# ME433.net
KiCad netlist of a schematic drawn in EAGLE
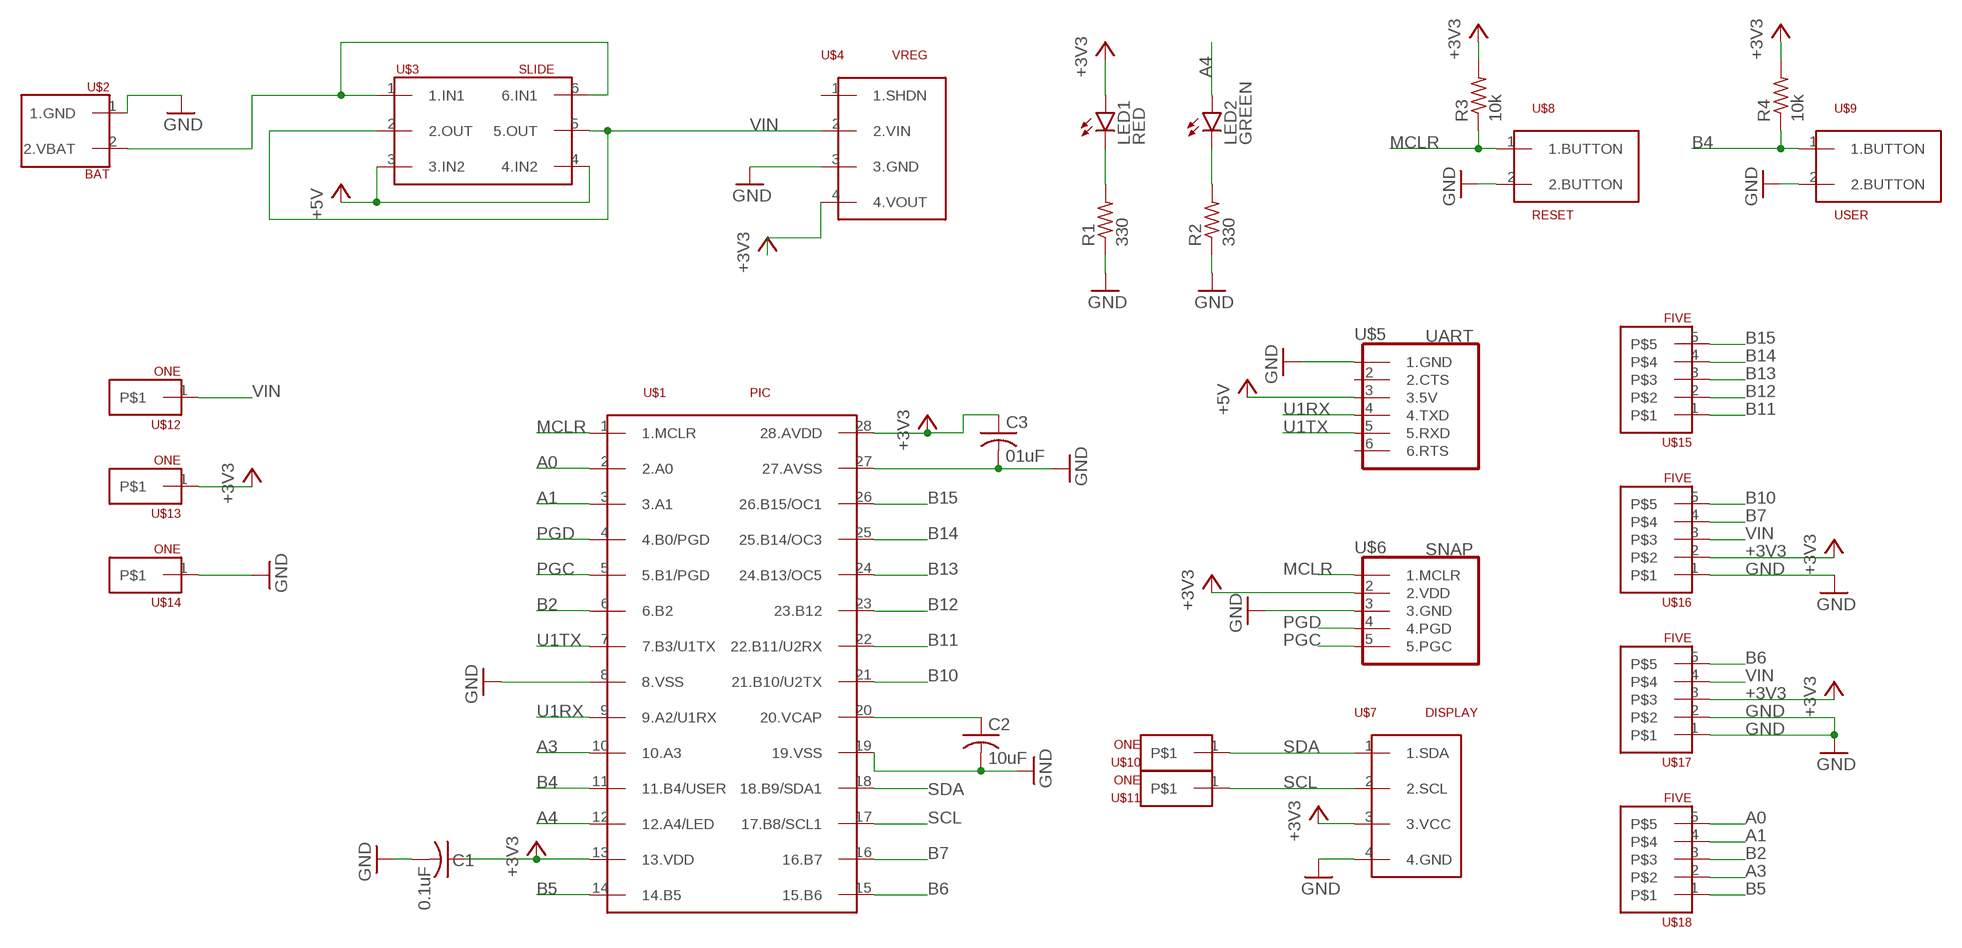
[diagram p0: schematic, sheet 1]

(export (version "E")
  (design (tool "Eeschema 10.0.6"))
  (components
    (comp (ref "C1")
      (value "0.1uF")
      (footprint "eagle-import:C025-024X044")
      (libsource (lib "eagle-import") (part "C-US025-024X044"))
    )
    (comp (ref "C2")
      (value "10uF")
      (footprint "eagle-import:C025-024X044")
      (libsource (lib "eagle-import") (part "C-US025-024X044"))
    )
    (comp (ref "C3")
      (value "01uF")
      (footprint "eagle-import:C025-024X044")
      (libsource (lib "eagle-import") (part "C-US025-024X044"))
    )
    (comp (ref "LED1")
      (value "RED")
      (footprint "eagle-import:LED3MM")
      (libsource (lib "eagle-import") (part "LED3MM"))
    )
    (comp (ref "LED2")
      (value "GREEN")
      (footprint "eagle-import:LED3MM")
      (libsource (lib "eagle-import") (part "LED3MM"))
    )
    (comp (ref "R1")
      (value "330")
      (footprint "eagle-import:0207_7")
      (libsource (lib "eagle-import") (part "R-US_0207/7"))
    )
    (comp (ref "R2")
      (value "330")
      (footprint "eagle-import:0207_7")
      (libsource (lib "eagle-import") (part "R-US_0207/7"))
    )
    (comp (ref "R3")
      (value "10k")
      (footprint "eagle-import:0207_7")
      (libsource (lib "eagle-import") (part "R-US_0207/7"))
    )
    (comp (ref "R4")
      (value "10k")
      (footprint "eagle-import:0207_7")
      (libsource (lib "eagle-import") (part "R-US_0207/7"))
    )
    (comp (ref "U$1")
      (value "PIC")
      (footprint "eagle-import:DIL28-3")
      (libsource (lib "eagle-import") (part "PIC"))
    )
    (comp (ref "U$2")
      (value "BAT")
      (footprint "eagle-import:BAT")
      (libsource (lib "eagle-import") (part "BAT"))
    )
    (comp (ref "U$3")
      (value "SLIDE")
      (footprint "eagle-import:SLIDE")
      (libsource (lib "eagle-import") (part "SLIDE"))
    )
    (comp (ref "U$4")
      (value "VREG")
      (footprint "eagle-import:VREG")
      (libsource (lib "eagle-import") (part "VREG"))
    )
    (comp (ref "U$5")
      (value "UART")
      (footprint "eagle-import:UART")
      (libsource (lib "eagle-import") (part "UART"))
    )
    (comp (ref "U$6")
      (value "SNAP")
      (footprint "eagle-import:SNAP")
      (libsource (lib "eagle-import") (part "SNAP"))
    )
    (comp (ref "U$7")
      (value "DISPLAY")
      (footprint "eagle-import:DISPLAY")
      (libsource (lib "eagle-import") (part "DISPLAY"))
    )
    (comp (ref "U$8")
      (value "RESET")
      (footprint "eagle-import:BUTTON")
      (libsource (lib "eagle-import") (part "BUTTON"))
    )
    (comp (ref "U$9")
      (value "USER")
      (footprint "eagle-import:BUTTON")
      (libsource (lib "eagle-import") (part "BUTTON"))
    )
    (comp (ref "U$10")
      (value "ONE")
      (footprint "eagle-import:ONE")
      (libsource (lib "eagle-import") (part "ONE"))
    )
    (comp (ref "U$11")
      (value "ONE")
      (footprint "eagle-import:ONE")
      (libsource (lib "eagle-import") (part "ONE"))
    )
    (comp (ref "U$12")
      (value "ONE")
      (footprint "eagle-import:ONE")
      (libsource (lib "eagle-import") (part "ONE"))
    )
    (comp (ref "U$13")
      (value "ONE")
      (footprint "eagle-import:ONE")
      (libsource (lib "eagle-import") (part "ONE"))
    )
    (comp (ref "U$14")
      (value "ONE")
      (footprint "eagle-import:ONE")
      (libsource (lib "eagle-import") (part "ONE"))
    )
    (comp (ref "U$15")
      (value "FIVE")
      (footprint "eagle-import:FIVE")
      (libsource (lib "eagle-import") (part "FIVE"))
    )
    (comp (ref "U$16")
      (value "FIVE")
      (footprint "eagle-import:FIVE")
      (libsource (lib "eagle-import") (part "FIVE"))
    )
    (comp (ref "U$17")
      (value "FIVE")
      (footprint "eagle-import:FIVE")
      (libsource (lib "eagle-import") (part "FIVE"))
    )
    (comp (ref "U$18")
      (value "FIVE")
      (footprint "eagle-import:FIVE")
      (libsource (lib "eagle-import") (part "FIVE"))
    )
  )
  (nets
    (net (code "1") (name "+3V3") (class "Default")
      (node (ref "C1") (pin "1") (pinfunction "1_1") (pintype "passive"))
      (node (ref "C3") (pin "1") (pinfunction "1_1") (pintype "passive"))
      (node (ref "LED1") (pin "A") (pinfunction "A_A") (pintype "passive"))
      (node (ref "R3") (pin "2") (pinfunction "2_2") (pintype "passive"))
      (node (ref "R4") (pin "2") (pinfunction "2_2") (pintype "passive"))
      (node (ref "U$1") (pin "13") (pinfunction "13.VDD_13") (pintype "bidirectional"))
      (node (ref "U$1") (pin "28") (pinfunction "28.AVDD_28") (pintype "bidirectional"))
      (node (ref "U$13") (pin "1") (pinfunction "P$1_1") (pintype "bidirectional"))
      (node (ref "U$16") (pin "2") (pinfunction "P$2_2") (pintype "bidirectional"))
      (node (ref "U$17") (pin "3") (pinfunction "P$3_3") (pintype "bidirectional"))
      (node (ref "U$4") (pin "4") (pinfunction "4.VOUT_4") (pintype "bidirectional"))
      (node (ref "U$6") (pin "2") (pinfunction "2.VDD_2") (pintype "bidirectional"))
      (node (ref "U$7") (pin "3") (pinfunction "3.VCC_3") (pintype "bidirectional"))
    )
    (net (code "2") (name "+5V") (class "Default")
      (node (ref "U$3") (pin "3") (pinfunction "3.IN2_3") (pintype "bidirectional"))
      (node (ref "U$3") (pin "4") (pinfunction "4.IN2_4") (pintype "bidirectional"))
      (node (ref "U$5") (pin "3") (pinfunction "3.5V_3") (pintype "bidirectional"))
    )
    (net (code "3") (name "/A0") (class "Default")
      (node (ref "U$1") (pin "2") (pinfunction "2.A0_2") (pintype "bidirectional"))
      (node (ref "U$18") (pin "5") (pinfunction "P$5_5") (pintype "bidirectional"))
    )
    (net (code "4") (name "/A1") (class "Default")
      (node (ref "U$1") (pin "3") (pinfunction "3.A1_3") (pintype "bidirectional"))
      (node (ref "U$18") (pin "4") (pinfunction "P$4_4") (pintype "bidirectional"))
    )
    (net (code "5") (name "/A3") (class "Default")
      (node (ref "U$1") (pin "10") (pinfunction "10.A3_10") (pintype "bidirectional"))
      (node (ref "U$18") (pin "2") (pinfunction "P$2_2") (pintype "bidirectional"))
    )
    (net (code "6") (name "/A4") (class "Default")
      (node (ref "LED2") (pin "A") (pinfunction "A_A") (pintype "passive"))
      (node (ref "U$1") (pin "12") (pinfunction "12.A4/LED_12") (pintype "bidirectional"))
    )
    (net (code "7") (name "/B2") (class "Default")
      (node (ref "U$1") (pin "6") (pinfunction "6.B2_6") (pintype "bidirectional"))
      (node (ref "U$18") (pin "3") (pinfunction "P$3_3") (pintype "bidirectional"))
    )
    (net (code "8") (name "/B4") (class "Default")
      (node (ref "R4") (pin "1") (pinfunction "1_1") (pintype "passive"))
      (node (ref "U$1") (pin "11") (pinfunction "11.B4/USER_11") (pintype "bidirectional"))
      (node (ref "U$9") (pin "1") (pinfunction "1.BUTTON_1") (pintype "bidirectional"))
    )
    (net (code "9") (name "/B5") (class "Default")
      (node (ref "U$1") (pin "14") (pinfunction "14.B5_14") (pintype "bidirectional"))
      (node (ref "U$18") (pin "1") (pinfunction "P$1_1") (pintype "bidirectional"))
    )
    (net (code "10") (name "/B6") (class "Default")
      (node (ref "U$1") (pin "15") (pinfunction "15.B6_15") (pintype "bidirectional"))
      (node (ref "U$17") (pin "5") (pinfunction "P$5_5") (pintype "bidirectional"))
    )
    (net (code "11") (name "/B7") (class "Default")
      (node (ref "U$1") (pin "16") (pinfunction "16.B7_16") (pintype "bidirectional"))
      (node (ref "U$16") (pin "4") (pinfunction "P$4_4") (pintype "bidirectional"))
    )
    (net (code "12") (name "/B10") (class "Default")
      (node (ref "U$1") (pin "21") (pinfunction "21.B10/U2TX_21") (pintype "bidirectional"))
      (node (ref "U$16") (pin "5") (pinfunction "P$5_5") (pintype "bidirectional"))
    )
    (net (code "13") (name "/B11") (class "Default")
      (node (ref "U$1") (pin "22") (pinfunction "22.B11/U2RX_22") (pintype "bidirectional"))
      (node (ref "U$15") (pin "1") (pinfunction "P$1_1") (pintype "bidirectional"))
    )
    (net (code "14") (name "/B12") (class "Default")
      (node (ref "U$1") (pin "23") (pinfunction "23.B12_23") (pintype "bidirectional"))
      (node (ref "U$15") (pin "2") (pinfunction "P$2_2") (pintype "bidirectional"))
    )
    (net (code "15") (name "/B13") (class "Default")
      (node (ref "U$1") (pin "24") (pinfunction "24.B13/OC5_24") (pintype "bidirectional"))
      (node (ref "U$15") (pin "3") (pinfunction "P$3_3") (pintype "bidirectional"))
    )
    (net (code "16") (name "/B14") (class "Default")
      (node (ref "U$1") (pin "25") (pinfunction "25.B14/OC3_25") (pintype "bidirectional"))
      (node (ref "U$15") (pin "4") (pinfunction "P$4_4") (pintype "bidirectional"))
    )
    (net (code "17") (name "/B15") (class "Default")
      (node (ref "U$1") (pin "26") (pinfunction "26.B15/OC1_26") (pintype "bidirectional"))
      (node (ref "U$15") (pin "5") (pinfunction "P$5_5") (pintype "bidirectional"))
    )
    (net (code "18") (name "/MCLR") (class "Default")
      (node (ref "R3") (pin "1") (pinfunction "1_1") (pintype "passive"))
      (node (ref "U$1") (pin "1") (pinfunction "1.MCLR_1") (pintype "bidirectional"))
      (node (ref "U$6") (pin "1") (pinfunction "1.MCLR_1") (pintype "bidirectional"))
      (node (ref "U$8") (pin "1") (pinfunction "1.BUTTON_1") (pintype "bidirectional"))
    )
    (net (code "19") (name "/PGC") (class "Default")
      (node (ref "U$1") (pin "5") (pinfunction "5.B1/PGD_5") (pintype "bidirectional"))
      (node (ref "U$6") (pin "5") (pinfunction "5.PGC_5") (pintype "bidirectional"))
    )
    (net (code "20") (name "/PGD") (class "Default")
      (node (ref "U$1") (pin "4") (pinfunction "4.B0/PGD_4") (pintype "bidirectional"))
      (node (ref "U$6") (pin "4") (pinfunction "4.PGD_4") (pintype "bidirectional"))
    )
    (net (code "21") (name "/SCL") (class "Default")
      (node (ref "U$1") (pin "17") (pinfunction "17.B8/SCL1_17") (pintype "bidirectional"))
      (node (ref "U$11") (pin "1") (pinfunction "P$1_1") (pintype "bidirectional"))
      (node (ref "U$7") (pin "2") (pinfunction "2.SCL_2") (pintype "bidirectional"))
    )
    (net (code "22") (name "/SDA") (class "Default")
      (node (ref "U$1") (pin "18") (pinfunction "18.B9/SDA1_18") (pintype "bidirectional"))
      (node (ref "U$10") (pin "1") (pinfunction "P$1_1") (pintype "bidirectional"))
      (node (ref "U$7") (pin "1") (pinfunction "1.SDA_1") (pintype "bidirectional"))
    )
    (net (code "23") (name "/U1RX") (class "Default")
      (node (ref "U$1") (pin "9") (pinfunction "9.A2/U1RX_9") (pintype "bidirectional"))
      (node (ref "U$5") (pin "4") (pinfunction "4.TXD_4") (pintype "bidirectional"))
    )
    (net (code "24") (name "/U1TX") (class "Default")
      (node (ref "U$1") (pin "7") (pinfunction "7.B3/U1TX_7") (pintype "bidirectional"))
      (node (ref "U$5") (pin "5") (pinfunction "5.RXD_5") (pintype "bidirectional"))
    )
    (net (code "25") (name "/VIN") (class "Default")
      (node (ref "U$12") (pin "1") (pinfunction "P$1_1") (pintype "bidirectional"))
      (node (ref "U$16") (pin "3") (pinfunction "P$3_3") (pintype "bidirectional"))
      (node (ref "U$17") (pin "4") (pinfunction "P$4_4") (pintype "bidirectional"))
      (node (ref "U$3") (pin "2") (pinfunction "2.OUT_2") (pintype "bidirectional"))
      (node (ref "U$3") (pin "5") (pinfunction "5.OUT_5") (pintype "bidirectional"))
      (node (ref "U$4") (pin "2") (pinfunction "2.VIN_2") (pintype "bidirectional"))
    )
    (net (code "26") (name "GND") (class "Default")
      (node (ref "C1") (pin "2") (pinfunction "2_2") (pintype "passive"))
      (node (ref "C2") (pin "2") (pinfunction "2_2") (pintype "passive"))
      (node (ref "C3") (pin "2") (pinfunction "2_2") (pintype "passive"))
      (node (ref "R1") (pin "1") (pinfunction "1_1") (pintype "passive"))
      (node (ref "R2") (pin "1") (pinfunction "1_1") (pintype "passive"))
      (node (ref "U$1") (pin "19") (pinfunction "19.VSS_19") (pintype "bidirectional"))
      (node (ref "U$1") (pin "27") (pinfunction "27.AVSS_27") (pintype "bidirectional"))
      (node (ref "U$1") (pin "8") (pinfunction "8.VSS_8") (pintype "bidirectional"))
      (node (ref "U$14") (pin "1") (pinfunction "P$1_1") (pintype "bidirectional"))
      (node (ref "U$16") (pin "1") (pinfunction "P$1_1") (pintype "bidirectional"))
      (node (ref "U$17") (pin "1") (pinfunction "P$1_1") (pintype "bidirectional"))
      (node (ref "U$17") (pin "2") (pinfunction "P$2_2") (pintype "bidirectional"))
      (node (ref "U$2") (pin "1") (pinfunction "1.GND_1") (pintype "bidirectional"))
      (node (ref "U$4") (pin "3") (pinfunction "3.GND_3") (pintype "bidirectional"))
      (node (ref "U$5") (pin "1") (pinfunction "1.GND_1") (pintype "bidirectional"))
      (node (ref "U$6") (pin "3") (pinfunction "3.GND_3") (pintype "bidirectional"))
      (node (ref "U$7") (pin "4") (pinfunction "4.GND_4") (pintype "bidirectional"))
      (node (ref "U$8") (pin "2") (pinfunction "2.BUTTON_2") (pintype "bidirectional"))
      (node (ref "U$9") (pin "2") (pinfunction "2.BUTTON_2") (pintype "bidirectional"))
    )
    (net (code "27") (name "Net-(LED1-C)") (class "Default")
      (node (ref "LED1") (pin "K") (pinfunction "C_K") (pintype "passive"))
      (node (ref "R1") (pin "2") (pinfunction "2_2") (pintype "passive"))
    )
    (net (code "28") (name "Net-(LED2-C)") (class "Default")
      (node (ref "LED2") (pin "K") (pinfunction "C_K") (pintype "passive"))
      (node (ref "R2") (pin "2") (pinfunction "2_2") (pintype "passive"))
    )
    (net (code "29") (name "Net-(U$1-20.VCAP)") (class "Default")
      (node (ref "C2") (pin "1") (pinfunction "1_1") (pintype "passive"))
      (node (ref "U$1") (pin "20") (pinfunction "20.VCAP_20") (pintype "bidirectional"))
    )
    (net (code "30") (name "Net-(U$2-2.VBAT)") (class "Default")
      (node (ref "U$2") (pin "2") (pinfunction "2.VBAT_2") (pintype "bidirectional"))
      (node (ref "U$3") (pin "1") (pinfunction "1.IN1_1") (pintype "bidirectional"))
      (node (ref "U$3") (pin "6") (pinfunction "6.IN1_6") (pintype "bidirectional"))
    )
    (net (code "31") (name "unconnected-(U$4-1.SHDN-Pad1)") (class "Default")
      (node (ref "U$4") (pin "1") (pinfunction "1.SHDN_1") (pintype "bidirectional"))
    )
    (net (code "32") (name "unconnected-(U$5-2.CTS-Pad2)") (class "Default")
      (node (ref "U$5") (pin "2") (pinfunction "2.CTS_2") (pintype "bidirectional"))
    )
    (net (code "33") (name "unconnected-(U$5-6.RTS-Pad6)") (class "Default")
      (node (ref "U$5") (pin "6") (pinfunction "6.RTS_6") (pintype "bidirectional"))
    )
  )
)
